# turbocharge.net
KiCad netlist of a schematic drawn in EAGLE
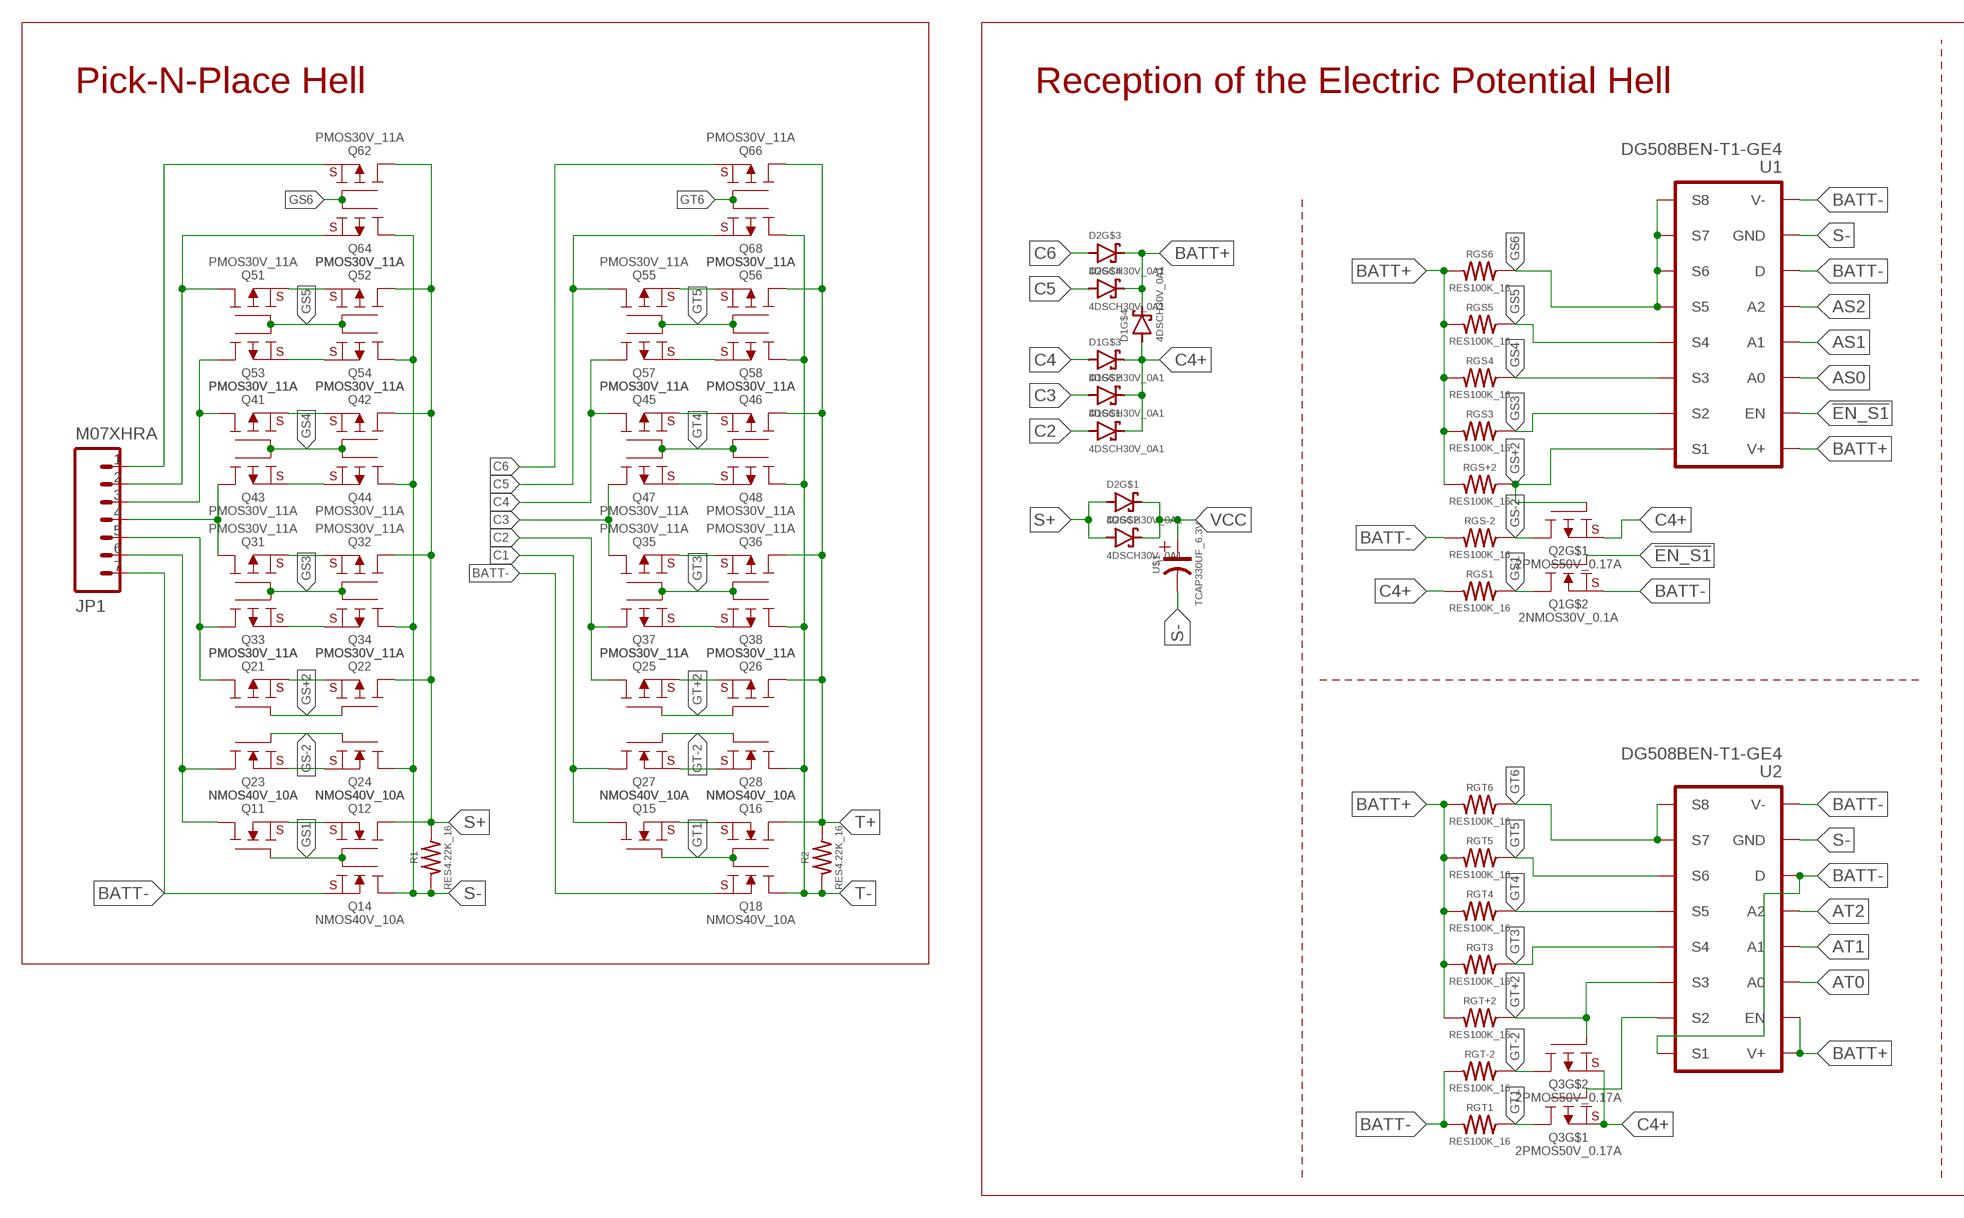
[diagram p0: schematic, sheet 1, part 1 of 2]
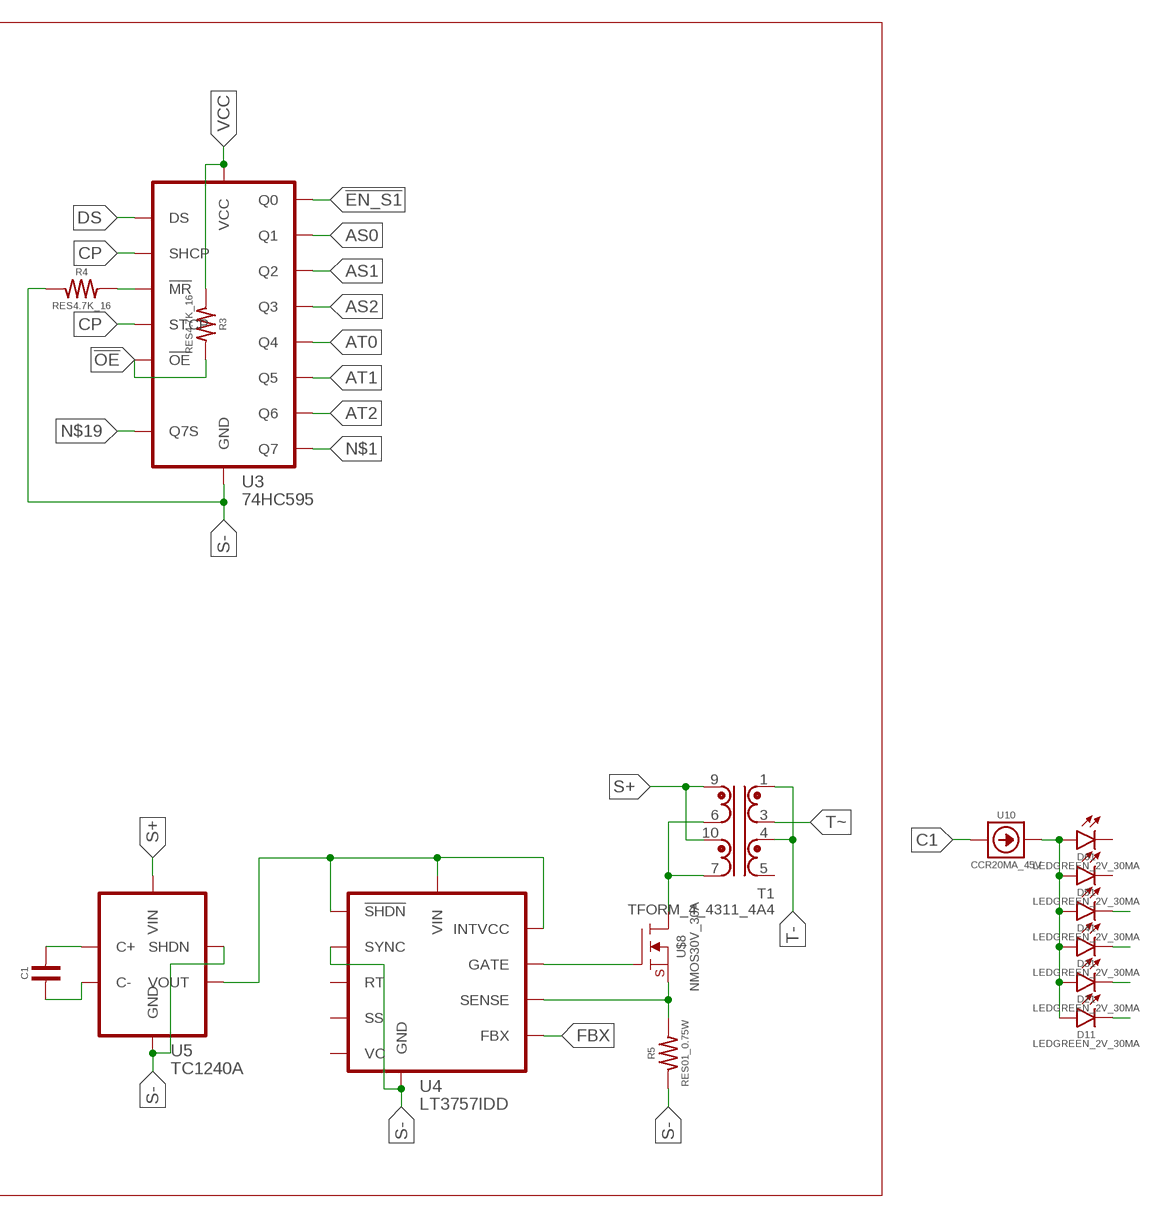
[diagram p1: schematic, sheet 1, part 2 of 2]

(export (version "E")
  (design (tool "Eeschema 10.0.6"))
  (components
    (comp (ref "C1")
      (value "CAP47UF_10V")
      (footprint "eagle-import:0805")
      (fields
        (field (name "DIGIKEY_PART_#") "445-8239-1-ND")
        (field (name "MANUFACTURER") "TDK Corporation")
        (field (name "MFG_PART_#") "C2012X5R1A476M125AC")
      )
      (libsource (lib "eagle-import") (part "CAP47UF_10V"))
    )
    (comp (ref "D1")
      (value "4DSCH30V_0A1")
      (footprint "eagle-import:8-HMD")
      (fields
        (field (name "DIGIKEY_PART_#") "RB521ZS8A30TE61CT-ND")
        (field (name "MANUFACTURER") "Rohm Semiconductor")
        (field (name "MFG_PART_#") "RB521ZS8A30TE61")
      )
      (libsource (lib "eagle-import") (part "4DSCH30V_0A1"))
    )
    (comp (ref "D2")
      (value "4DSCH30V_0A1")
      (footprint "eagle-import:8-HMD")
      (fields
        (field (name "DIGIKEY_PART_#") "RB521ZS8A30TE61CT-ND")
        (field (name "MANUFACTURER") "Rohm Semiconductor")
        (field (name "MFG_PART_#") "RB521ZS8A30TE61")
      )
      (libsource (lib "eagle-import") (part "4DSCH30V_0A1"))
    )
    (comp (ref "D11")
      (value "LEDGREEN_2V_30MA")
      (footprint "eagle-import:0603+")
      (fields
        (field (name "DIGIKEY_PART_#") "160-1435-1-ND")
        (field (name "MANUFACTURER") "Lite-On Inc.")
        (field (name "MFG_PART_#") "LTST-C190KGKT")
      )
      (libsource (lib "eagle-import") (part "LEDGREEN_2V_30MA"))
    )
    (comp (ref "D21")
      (value "LEDGREEN_2V_30MA")
      (footprint "eagle-import:0603+")
      (fields
        (field (name "DIGIKEY_PART_#") "160-1435-1-ND")
        (field (name "MANUFACTURER") "Lite-On Inc.")
        (field (name "MFG_PART_#") "LTST-C190KGKT")
      )
      (libsource (lib "eagle-import") (part "LEDGREEN_2V_30MA"))
    )
    (comp (ref "D31")
      (value "LEDGREEN_2V_30MA")
      (footprint "eagle-import:0603+")
      (fields
        (field (name "DIGIKEY_PART_#") "160-1435-1-ND")
        (field (name "MANUFACTURER") "Lite-On Inc.")
        (field (name "MFG_PART_#") "LTST-C190KGKT")
      )
      (libsource (lib "eagle-import") (part "LEDGREEN_2V_30MA"))
    )
    (comp (ref "D41")
      (value "LEDGREEN_2V_30MA")
      (footprint "eagle-import:0603+")
      (fields
        (field (name "DIGIKEY_PART_#") "160-1435-1-ND")
        (field (name "MANUFACTURER") "Lite-On Inc.")
        (field (name "MFG_PART_#") "LTST-C190KGKT")
      )
      (libsource (lib "eagle-import") (part "LEDGREEN_2V_30MA"))
    )
    (comp (ref "D51")
      (value "LEDGREEN_2V_30MA")
      (footprint "eagle-import:0603+")
      (fields
        (field (name "DIGIKEY_PART_#") "160-1435-1-ND")
        (field (name "MANUFACTURER") "Lite-On Inc.")
        (field (name "MFG_PART_#") "LTST-C190KGKT")
      )
      (libsource (lib "eagle-import") (part "LEDGREEN_2V_30MA"))
    )
    (comp (ref "D61")
      (value "LEDGREEN_2V_30MA")
      (footprint "eagle-import:0603+")
      (fields
        (field (name "DIGIKEY_PART_#") "160-1435-1-ND")
        (field (name "MANUFACTURER") "Lite-On Inc.")
        (field (name "MFG_PART_#") "LTST-C190KGKT")
      )
      (libsource (lib "eagle-import") (part "LEDGREEN_2V_30MA"))
    )
    (comp (ref "JP1")
      (value "M07XHRA")
      (footprint "eagle-import:XH07-RA")
      (fields
        (field (name "DIGIKEY_PART_#") "455-2240-ND")
        (field (name "MANUFACTURER") "JST Sales America Inc.")
        (field (name "MFG_PART_#") "S7B-XH-A(LF)(SN)")
      )
      (libsource (lib "eagle-import") (part "M07XHRA"))
    )
    (comp (ref "Q1")
      (value "2NMOS30V_0.1A")
      (footprint "eagle-import:SOT-666")
      (fields
        (field (name "DIGIKEY_PART_#") "FC6943010RCT-ND")
        (field (name "MANUFACTURER") "Panasonic Electronic Components")
        (field (name "MFG_PART_#") "FC6943010R")
      )
      (libsource (lib "eagle-import") (part "2NMOS30V_0.1A"))
    )
    (comp (ref "Q2")
      (value "2PMOS50V_0.17A")
      (footprint "eagle-import:SOT-666")
      (fields
        (field (name "DIGIKEY_PART_#") "568-10474-1-ND")
        (field (name "MANUFACTURER") "NXP Semiconductors")
        (field (name "MFG_PART_#") "BSS84AKV,115")
      )
      (libsource (lib "eagle-import") (part "2PMOS50V_0.17A"))
    )
    (comp (ref "Q3")
      (value "2PMOS50V_0.17A")
      (footprint "eagle-import:SOT-666")
      (fields
        (field (name "DIGIKEY_PART_#") "568-10474-1-ND")
        (field (name "MANUFACTURER") "NXP Semiconductors")
        (field (name "MFG_PART_#") "BSS84AKV,115")
      )
      (libsource (lib "eagle-import") (part "2PMOS50V_0.17A"))
    )
    (comp (ref "Q11")
      (value "NMOS40V_10A")
      (footprint "eagle-import:6-POWERWDFN")
      (fields
        (field (name "DIGIKEY_PART_#") "FDMA7670CT-ND")
        (field (name "MANUFACTURER") "Fairchild Semiconductor")
        (field (name "MFG_PART_#") "FDMA7670")
      )
      (libsource (lib "eagle-import") (part "NMOS40V_10A"))
    )
    (comp (ref "Q12")
      (value "NMOS40V_10A")
      (footprint "eagle-import:6-POWERWDFN")
      (fields
        (field (name "DIGIKEY_PART_#") "FDMA7670CT-ND")
        (field (name "MANUFACTURER") "Fairchild Semiconductor")
        (field (name "MFG_PART_#") "FDMA7670")
      )
      (libsource (lib "eagle-import") (part "NMOS40V_10A"))
    )
    (comp (ref "Q14")
      (value "NMOS40V_10A")
      (footprint "eagle-import:6-POWERWDFN")
      (fields
        (field (name "DIGIKEY_PART_#") "FDMA7670CT-ND")
        (field (name "MANUFACTURER") "Fairchild Semiconductor")
        (field (name "MFG_PART_#") "FDMA7670")
      )
      (libsource (lib "eagle-import") (part "NMOS40V_10A"))
    )
    (comp (ref "Q15")
      (value "NMOS40V_10A")
      (footprint "eagle-import:6-POWERWDFN")
      (fields
        (field (name "DIGIKEY_PART_#") "FDMA7670CT-ND")
        (field (name "MANUFACTURER") "Fairchild Semiconductor")
        (field (name "MFG_PART_#") "FDMA7670")
      )
      (libsource (lib "eagle-import") (part "NMOS40V_10A"))
    )
    (comp (ref "Q16")
      (value "NMOS40V_10A")
      (footprint "eagle-import:6-POWERWDFN")
      (fields
        (field (name "DIGIKEY_PART_#") "FDMA7670CT-ND")
        (field (name "MANUFACTURER") "Fairchild Semiconductor")
        (field (name "MFG_PART_#") "FDMA7670")
      )
      (libsource (lib "eagle-import") (part "NMOS40V_10A"))
    )
    (comp (ref "Q18")
      (value "NMOS40V_10A")
      (footprint "eagle-import:6-POWERWDFN")
      (fields
        (field (name "DIGIKEY_PART_#") "FDMA7670CT-ND")
        (field (name "MANUFACTURER") "Fairchild Semiconductor")
        (field (name "MFG_PART_#") "FDMA7670")
      )
      (libsource (lib "eagle-import") (part "NMOS40V_10A"))
    )
    (comp (ref "Q21")
      (value "PMOS30V_11A")
      (footprint "eagle-import:6-POWERWDFN")
      (fields
        (field (name "DIGIKEY_PART_#") "FDMA6676PZCT-ND")
        (field (name "MANUFACTURER") "Fairchild Semiconductor")
        (field (name "MFG_PART_#") "FDMA6676PZ")
      )
      (libsource (lib "eagle-import") (part "PMOS30V_11A"))
    )
    (comp (ref "Q22")
      (value "PMOS30V_11A")
      (footprint "eagle-import:6-POWERWDFN")
      (fields
        (field (name "DIGIKEY_PART_#") "FDMA6676PZCT-ND")
        (field (name "MANUFACTURER") "Fairchild Semiconductor")
        (field (name "MFG_PART_#") "FDMA6676PZ")
      )
      (libsource (lib "eagle-import") (part "PMOS30V_11A"))
    )
    (comp (ref "Q23")
      (value "NMOS40V_10A")
      (footprint "eagle-import:6-POWERWDFN")
      (fields
        (field (name "DIGIKEY_PART_#") "FDMA7670CT-ND")
        (field (name "MANUFACTURER") "Fairchild Semiconductor")
        (field (name "MFG_PART_#") "FDMA7670")
      )
      (libsource (lib "eagle-import") (part "NMOS40V_10A"))
    )
    (comp (ref "Q24")
      (value "NMOS40V_10A")
      (footprint "eagle-import:6-POWERWDFN")
      (fields
        (field (name "DIGIKEY_PART_#") "FDMA7670CT-ND")
        (field (name "MANUFACTURER") "Fairchild Semiconductor")
        (field (name "MFG_PART_#") "FDMA7670")
      )
      (libsource (lib "eagle-import") (part "NMOS40V_10A"))
    )
    (comp (ref "Q25")
      (value "PMOS30V_11A")
      (footprint "eagle-import:6-POWERWDFN")
      (fields
        (field (name "DIGIKEY_PART_#") "FDMA6676PZCT-ND")
        (field (name "MANUFACTURER") "Fairchild Semiconductor")
        (field (name "MFG_PART_#") "FDMA6676PZ")
      )
      (libsource (lib "eagle-import") (part "PMOS30V_11A"))
    )
    (comp (ref "Q26")
      (value "PMOS30V_11A")
      (footprint "eagle-import:6-POWERWDFN")
      (fields
        (field (name "DIGIKEY_PART_#") "FDMA6676PZCT-ND")
        (field (name "MANUFACTURER") "Fairchild Semiconductor")
        (field (name "MFG_PART_#") "FDMA6676PZ")
      )
      (libsource (lib "eagle-import") (part "PMOS30V_11A"))
    )
    (comp (ref "Q27")
      (value "NMOS40V_10A")
      (footprint "eagle-import:6-POWERWDFN")
      (fields
        (field (name "DIGIKEY_PART_#") "FDMA7670CT-ND")
        (field (name "MANUFACTURER") "Fairchild Semiconductor")
        (field (name "MFG_PART_#") "FDMA7670")
      )
      (libsource (lib "eagle-import") (part "NMOS40V_10A"))
    )
    (comp (ref "Q28")
      (value "NMOS40V_10A")
      (footprint "eagle-import:6-POWERWDFN")
      (fields
        (field (name "DIGIKEY_PART_#") "FDMA7670CT-ND")
        (field (name "MANUFACTURER") "Fairchild Semiconductor")
        (field (name "MFG_PART_#") "FDMA7670")
      )
      (libsource (lib "eagle-import") (part "NMOS40V_10A"))
    )
    (comp (ref "Q31")
      (value "PMOS30V_11A")
      (footprint "eagle-import:6-POWERWDFN")
      (fields
        (field (name "DIGIKEY_PART_#") "FDMA6676PZCT-ND")
        (field (name "MANUFACTURER") "Fairchild Semiconductor")
        (field (name "MFG_PART_#") "FDMA6676PZ")
      )
      (libsource (lib "eagle-import") (part "PMOS30V_11A"))
    )
    (comp (ref "Q32")
      (value "PMOS30V_11A")
      (footprint "eagle-import:6-POWERWDFN")
      (fields
        (field (name "DIGIKEY_PART_#") "FDMA6676PZCT-ND")
        (field (name "MANUFACTURER") "Fairchild Semiconductor")
        (field (name "MFG_PART_#") "FDMA6676PZ")
      )
      (libsource (lib "eagle-import") (part "PMOS30V_11A"))
    )
    (comp (ref "Q33")
      (value "PMOS30V_11A")
      (footprint "eagle-import:6-POWERWDFN")
      (fields
        (field (name "DIGIKEY_PART_#") "FDMA6676PZCT-ND")
        (field (name "MANUFACTURER") "Fairchild Semiconductor")
        (field (name "MFG_PART_#") "FDMA6676PZ")
      )
      (libsource (lib "eagle-import") (part "PMOS30V_11A"))
    )
    (comp (ref "Q34")
      (value "PMOS30V_11A")
      (footprint "eagle-import:6-POWERWDFN")
      (fields
        (field (name "DIGIKEY_PART_#") "FDMA6676PZCT-ND")
        (field (name "MANUFACTURER") "Fairchild Semiconductor")
        (field (name "MFG_PART_#") "FDMA6676PZ")
      )
      (libsource (lib "eagle-import") (part "PMOS30V_11A"))
    )
    (comp (ref "Q35")
      (value "PMOS30V_11A")
      (footprint "eagle-import:6-POWERWDFN")
      (fields
        (field (name "DIGIKEY_PART_#") "FDMA6676PZCT-ND")
        (field (name "MANUFACTURER") "Fairchild Semiconductor")
        (field (name "MFG_PART_#") "FDMA6676PZ")
      )
      (libsource (lib "eagle-import") (part "PMOS30V_11A"))
    )
    (comp (ref "Q36")
      (value "PMOS30V_11A")
      (footprint "eagle-import:6-POWERWDFN")
      (fields
        (field (name "DIGIKEY_PART_#") "FDMA6676PZCT-ND")
        (field (name "MANUFACTURER") "Fairchild Semiconductor")
        (field (name "MFG_PART_#") "FDMA6676PZ")
      )
      (libsource (lib "eagle-import") (part "PMOS30V_11A"))
    )
    (comp (ref "Q37")
      (value "PMOS30V_11A")
      (footprint "eagle-import:6-POWERWDFN")
      (fields
        (field (name "DIGIKEY_PART_#") "FDMA6676PZCT-ND")
        (field (name "MANUFACTURER") "Fairchild Semiconductor")
        (field (name "MFG_PART_#") "FDMA6676PZ")
      )
      (libsource (lib "eagle-import") (part "PMOS30V_11A"))
    )
    (comp (ref "Q38")
      (value "PMOS30V_11A")
      (footprint "eagle-import:6-POWERWDFN")
      (fields
        (field (name "DIGIKEY_PART_#") "FDMA6676PZCT-ND")
        (field (name "MANUFACTURER") "Fairchild Semiconductor")
        (field (name "MFG_PART_#") "FDMA6676PZ")
      )
      (libsource (lib "eagle-import") (part "PMOS30V_11A"))
    )
    (comp (ref "Q41")
      (value "PMOS30V_11A")
      (footprint "eagle-import:6-POWERWDFN")
      (fields
        (field (name "DIGIKEY_PART_#") "FDMA6676PZCT-ND")
        (field (name "MANUFACTURER") "Fairchild Semiconductor")
        (field (name "MFG_PART_#") "FDMA6676PZ")
      )
      (libsource (lib "eagle-import") (part "PMOS30V_11A"))
    )
    (comp (ref "Q42")
      (value "PMOS30V_11A")
      (footprint "eagle-import:6-POWERWDFN")
      (fields
        (field (name "DIGIKEY_PART_#") "FDMA6676PZCT-ND")
        (field (name "MANUFACTURER") "Fairchild Semiconductor")
        (field (name "MFG_PART_#") "FDMA6676PZ")
      )
      (libsource (lib "eagle-import") (part "PMOS30V_11A"))
    )
    (comp (ref "Q43")
      (value "PMOS30V_11A")
      (footprint "eagle-import:6-POWERWDFN")
      (fields
        (field (name "DIGIKEY_PART_#") "FDMA6676PZCT-ND")
        (field (name "MANUFACTURER") "Fairchild Semiconductor")
        (field (name "MFG_PART_#") "FDMA6676PZ")
      )
      (libsource (lib "eagle-import") (part "PMOS30V_11A"))
    )
    (comp (ref "Q44")
      (value "PMOS30V_11A")
      (footprint "eagle-import:6-POWERWDFN")
      (fields
        (field (name "DIGIKEY_PART_#") "FDMA6676PZCT-ND")
        (field (name "MANUFACTURER") "Fairchild Semiconductor")
        (field (name "MFG_PART_#") "FDMA6676PZ")
      )
      (libsource (lib "eagle-import") (part "PMOS30V_11A"))
    )
    (comp (ref "Q45")
      (value "PMOS30V_11A")
      (footprint "eagle-import:6-POWERWDFN")
      (fields
        (field (name "DIGIKEY_PART_#") "FDMA6676PZCT-ND")
        (field (name "MANUFACTURER") "Fairchild Semiconductor")
        (field (name "MFG_PART_#") "FDMA6676PZ")
      )
      (libsource (lib "eagle-import") (part "PMOS30V_11A"))
    )
    (comp (ref "Q46")
      (value "PMOS30V_11A")
      (footprint "eagle-import:6-POWERWDFN")
      (fields
        (field (name "DIGIKEY_PART_#") "FDMA6676PZCT-ND")
        (field (name "MANUFACTURER") "Fairchild Semiconductor")
        (field (name "MFG_PART_#") "FDMA6676PZ")
      )
      (libsource (lib "eagle-import") (part "PMOS30V_11A"))
    )
    (comp (ref "Q47")
      (value "PMOS30V_11A")
      (footprint "eagle-import:6-POWERWDFN")
      (fields
        (field (name "DIGIKEY_PART_#") "FDMA6676PZCT-ND")
        (field (name "MANUFACTURER") "Fairchild Semiconductor")
        (field (name "MFG_PART_#") "FDMA6676PZ")
      )
      (libsource (lib "eagle-import") (part "PMOS30V_11A"))
    )
    (comp (ref "Q48")
      (value "PMOS30V_11A")
      (footprint "eagle-import:6-POWERWDFN")
      (fields
        (field (name "DIGIKEY_PART_#") "FDMA6676PZCT-ND")
        (field (name "MANUFACTURER") "Fairchild Semiconductor")
        (field (name "MFG_PART_#") "FDMA6676PZ")
      )
      (libsource (lib "eagle-import") (part "PMOS30V_11A"))
    )
    (comp (ref "Q51")
      (value "PMOS30V_11A")
      (footprint "eagle-import:6-POWERWDFN")
      (fields
        (field (name "DIGIKEY_PART_#") "FDMA6676PZCT-ND")
        (field (name "MANUFACTURER") "Fairchild Semiconductor")
        (field (name "MFG_PART_#") "FDMA6676PZ")
      )
      (libsource (lib "eagle-import") (part "PMOS30V_11A"))
    )
    (comp (ref "Q52")
      (value "PMOS30V_11A")
      (footprint "eagle-import:6-POWERWDFN")
      (fields
        (field (name "DIGIKEY_PART_#") "FDMA6676PZCT-ND")
        (field (name "MANUFACTURER") "Fairchild Semiconductor")
        (field (name "MFG_PART_#") "FDMA6676PZ")
      )
      (libsource (lib "eagle-import") (part "PMOS30V_11A"))
    )
    (comp (ref "Q53")
      (value "PMOS30V_11A")
      (footprint "eagle-import:6-POWERWDFN")
      (fields
        (field (name "DIGIKEY_PART_#") "FDMA6676PZCT-ND")
        (field (name "MANUFACTURER") "Fairchild Semiconductor")
        (field (name "MFG_PART_#") "FDMA6676PZ")
      )
      (libsource (lib "eagle-import") (part "PMOS30V_11A"))
    )
    (comp (ref "Q54")
      (value "PMOS30V_11A")
      (footprint "eagle-import:6-POWERWDFN")
      (fields
        (field (name "DIGIKEY_PART_#") "FDMA6676PZCT-ND")
        (field (name "MANUFACTURER") "Fairchild Semiconductor")
        (field (name "MFG_PART_#") "FDMA6676PZ")
      )
      (libsource (lib "eagle-import") (part "PMOS30V_11A"))
    )
    (comp (ref "Q55")
      (value "PMOS30V_11A")
      (footprint "eagle-import:6-POWERWDFN")
      (fields
        (field (name "DIGIKEY_PART_#") "FDMA6676PZCT-ND")
        (field (name "MANUFACTURER") "Fairchild Semiconductor")
        (field (name "MFG_PART_#") "FDMA6676PZ")
      )
      (libsource (lib "eagle-import") (part "PMOS30V_11A"))
    )
    (comp (ref "Q56")
      (value "PMOS30V_11A")
      (footprint "eagle-import:6-POWERWDFN")
      (fields
        (field (name "DIGIKEY_PART_#") "FDMA6676PZCT-ND")
        (field (name "MANUFACTURER") "Fairchild Semiconductor")
        (field (name "MFG_PART_#") "FDMA6676PZ")
      )
      (libsource (lib "eagle-import") (part "PMOS30V_11A"))
    )
    (comp (ref "Q57")
      (value "PMOS30V_11A")
      (footprint "eagle-import:6-POWERWDFN")
      (fields
        (field (name "DIGIKEY_PART_#") "FDMA6676PZCT-ND")
        (field (name "MANUFACTURER") "Fairchild Semiconductor")
        (field (name "MFG_PART_#") "FDMA6676PZ")
      )
      (libsource (lib "eagle-import") (part "PMOS30V_11A"))
    )
    (comp (ref "Q58")
      (value "PMOS30V_11A")
      (footprint "eagle-import:6-POWERWDFN")
      (fields
        (field (name "DIGIKEY_PART_#") "FDMA6676PZCT-ND")
        (field (name "MANUFACTURER") "Fairchild Semiconductor")
        (field (name "MFG_PART_#") "FDMA6676PZ")
      )
      (libsource (lib "eagle-import") (part "PMOS30V_11A"))
    )
    (comp (ref "Q62")
      (value "PMOS30V_11A")
      (footprint "eagle-import:6-POWERWDFN")
      (fields
        (field (name "DIGIKEY_PART_#") "FDMA6676PZCT-ND")
        (field (name "MANUFACTURER") "Fairchild Semiconductor")
        (field (name "MFG_PART_#") "FDMA6676PZ")
      )
      (libsource (lib "eagle-import") (part "PMOS30V_11A"))
    )
    (comp (ref "Q64")
      (value "PMOS30V_11A")
      (footprint "eagle-import:6-POWERWDFN")
      (fields
        (field (name "DIGIKEY_PART_#") "FDMA6676PZCT-ND")
        (field (name "MANUFACTURER") "Fairchild Semiconductor")
        (field (name "MFG_PART_#") "FDMA6676PZ")
      )
      (libsource (lib "eagle-import") (part "PMOS30V_11A"))
    )
    (comp (ref "Q66")
      (value "PMOS30V_11A")
      (footprint "eagle-import:6-POWERWDFN")
      (fields
        (field (name "DIGIKEY_PART_#") "FDMA6676PZCT-ND")
        (field (name "MANUFACTURER") "Fairchild Semiconductor")
        (field (name "MFG_PART_#") "FDMA6676PZ")
      )
      (libsource (lib "eagle-import") (part "PMOS30V_11A"))
    )
    (comp (ref "Q68")
      (value "PMOS30V_11A")
      (footprint "eagle-import:6-POWERWDFN")
      (fields
        (field (name "DIGIKEY_PART_#") "FDMA6676PZCT-ND")
        (field (name "MANUFACTURER") "Fairchild Semiconductor")
        (field (name "MFG_PART_#") "FDMA6676PZ")
      )
      (libsource (lib "eagle-import") (part "PMOS30V_11A"))
    )
    (comp (ref "R1")
      (value "RES4.22K_16")
      (footprint "eagle-import:0402")
      (fields
        (field (name "DIGIKEY_PART_#") "541-4.22KLCT-ND")
        (field (name "MANUFACTURER") "Vishay Dale")
        (field (name "MFG_PART_#") "CRCW04024K22FKED")
      )
      (libsource (lib "eagle-import") (part "RES4.22K_16"))
    )
    (comp (ref "R2")
      (value "RES4.22K_16")
      (footprint "eagle-import:0402")
      (fields
        (field (name "DIGIKEY_PART_#") "541-4.22KLCT-ND")
        (field (name "MANUFACTURER") "Vishay Dale")
        (field (name "MFG_PART_#") "CRCW04024K22FKED")
      )
      (libsource (lib "eagle-import") (part "RES4.22K_16"))
    )
    (comp (ref "R3")
      (value "RES4.7K_16")
      (footprint "eagle-import:0402")
      (fields
        (field (name "DIGIKEY_PART_#") "541-4.70KLCT-ND")
        (field (name "MANUFACTURER") "Vishay Dale")
        (field (name "MFG_PART_#") "CRCW04024K70FKED")
      )
      (libsource (lib "eagle-import") (part "RES4.7K_16"))
    )
    (comp (ref "R4")
      (value "RES4.7K_16")
      (footprint "eagle-import:0402")
      (fields
        (field (name "DIGIKEY_PART_#") "541-4.70KLCT-ND")
        (field (name "MANUFACTURER") "Vishay Dale")
        (field (name "MFG_PART_#") "CRCW04024K70FKED")
      )
      (libsource (lib "eagle-import") (part "RES4.7K_16"))
    )
    (comp (ref "R5")
      (value "RES01_0.75W")
      (footprint "eagle-import:1206")
      (fields
        (field (name "DIGIKEY_PART_#") "408-1570-1-ND")
        (field (name "MANUFACTURER") "Susumu")
        (field (name "MFG_PART_#") "KRL1632E-M-R010-F-T5")
      )
      (libsource (lib "eagle-import") (part "RES01_0.75W"))
    )
    (comp (ref "RGS+2")
      (value "RES100K_16")
      (footprint "eagle-import:0402")
      (fields
        (field (name "DIGIKEY_PART_#") "541-100KLCT-ND")
        (field (name "MANUFACTURER") "Vishay Dale")
        (field (name "MFG_PART_#") "CRCW0402100KFKED")
      )
      (libsource (lib "eagle-import") (part "RES100K_16"))
    )
    (comp (ref "RGS-2")
      (value "RES100K_16")
      (footprint "eagle-import:0402")
      (fields
        (field (name "DIGIKEY_PART_#") "541-100KLCT-ND")
        (field (name "MANUFACTURER") "Vishay Dale")
        (field (name "MFG_PART_#") "CRCW0402100KFKED")
      )
      (libsource (lib "eagle-import") (part "RES100K_16"))
    )
    (comp (ref "RGS1")
      (value "RES100K_16")
      (footprint "eagle-import:0402")
      (fields
        (field (name "DIGIKEY_PART_#") "541-100KLCT-ND")
        (field (name "MANUFACTURER") "Vishay Dale")
        (field (name "MFG_PART_#") "CRCW0402100KFKED")
      )
      (libsource (lib "eagle-import") (part "RES100K_16"))
    )
    (comp (ref "RGS3")
      (value "RES100K_16")
      (footprint "eagle-import:0402")
      (fields
        (field (name "DIGIKEY_PART_#") "541-100KLCT-ND")
        (field (name "MANUFACTURER") "Vishay Dale")
        (field (name "MFG_PART_#") "CRCW0402100KFKED")
      )
      (libsource (lib "eagle-import") (part "RES100K_16"))
    )
    (comp (ref "RGS4")
      (value "RES100K_16")
      (footprint "eagle-import:0402")
      (fields
        (field (name "DIGIKEY_PART_#") "541-100KLCT-ND")
        (field (name "MANUFACTURER") "Vishay Dale")
        (field (name "MFG_PART_#") "CRCW0402100KFKED")
      )
      (libsource (lib "eagle-import") (part "RES100K_16"))
    )
    (comp (ref "RGS5")
      (value "RES100K_16")
      (footprint "eagle-import:0402")
      (fields
        (field (name "DIGIKEY_PART_#") "541-100KLCT-ND")
        (field (name "MANUFACTURER") "Vishay Dale")
        (field (name "MFG_PART_#") "CRCW0402100KFKED")
      )
      (libsource (lib "eagle-import") (part "RES100K_16"))
    )
    (comp (ref "RGS6")
      (value "RES100K_16")
      (footprint "eagle-import:0402")
      (fields
        (field (name "DIGIKEY_PART_#") "541-100KLCT-ND")
        (field (name "MANUFACTURER") "Vishay Dale")
        (field (name "MFG_PART_#") "CRCW0402100KFKED")
      )
      (libsource (lib "eagle-import") (part "RES100K_16"))
    )
    (comp (ref "RGT+2")
      (value "RES100K_16")
      (footprint "eagle-import:0402")
      (fields
        (field (name "DIGIKEY_PART_#") "541-100KLCT-ND")
        (field (name "MANUFACTURER") "Vishay Dale")
        (field (name "MFG_PART_#") "CRCW0402100KFKED")
      )
      (libsource (lib "eagle-import") (part "RES100K_16"))
    )
    (comp (ref "RGT-2")
      (value "RES100K_16")
      (footprint "eagle-import:0402")
      (fields
        (field (name "DIGIKEY_PART_#") "541-100KLCT-ND")
        (field (name "MANUFACTURER") "Vishay Dale")
        (field (name "MFG_PART_#") "CRCW0402100KFKED")
      )
      (libsource (lib "eagle-import") (part "RES100K_16"))
    )
    (comp (ref "RGT1")
      (value "RES100K_16")
      (footprint "eagle-import:0402")
      (fields
        (field (name "DIGIKEY_PART_#") "541-100KLCT-ND")
        (field (name "MANUFACTURER") "Vishay Dale")
        (field (name "MFG_PART_#") "CRCW0402100KFKED")
      )
      (libsource (lib "eagle-import") (part "RES100K_16"))
    )
    (comp (ref "RGT3")
      (value "RES100K_16")
      (footprint "eagle-import:0402")
      (fields
        (field (name "DIGIKEY_PART_#") "541-100KLCT-ND")
        (field (name "MANUFACTURER") "Vishay Dale")
        (field (name "MFG_PART_#") "CRCW0402100KFKED")
      )
      (libsource (lib "eagle-import") (part "RES100K_16"))
    )
    (comp (ref "RGT4")
      (value "RES100K_16")
      (footprint "eagle-import:0402")
      (fields
        (field (name "DIGIKEY_PART_#") "541-100KLCT-ND")
        (field (name "MANUFACTURER") "Vishay Dale")
        (field (name "MFG_PART_#") "CRCW0402100KFKED")
      )
      (libsource (lib "eagle-import") (part "RES100K_16"))
    )
    (comp (ref "RGT5")
      (value "RES100K_16")
      (footprint "eagle-import:0402")
      (fields
        (field (name "DIGIKEY_PART_#") "541-100KLCT-ND")
        (field (name "MANUFACTURER") "Vishay Dale")
        (field (name "MFG_PART_#") "CRCW0402100KFKED")
      )
      (libsource (lib "eagle-import") (part "RES100K_16"))
    )
    (comp (ref "RGT6")
      (value "RES100K_16")
      (footprint "eagle-import:0402")
      (fields
        (field (name "DIGIKEY_PART_#") "541-100KLCT-ND")
        (field (name "MANUFACTURER") "Vishay Dale")
        (field (name "MFG_PART_#") "CRCW0402100KFKED")
      )
      (libsource (lib "eagle-import") (part "RES100K_16"))
    )
    (comp (ref "T1")
      (value "TFORM_4_4311_4A4")
      (footprint "eagle-import:EPQ13")
      (fields
        (field (name "DIGIKEY_PART_#") "732-6198-1-ND")
        (field (name "MANUFACTURER") "Wurth Electronics Inc")
        (field (name "MFG_PART_#") "7491195501")
      )
      (libsource (lib "eagle-import") (part "TFORM_4_4311_4A4"))
    )
    (comp (ref "U$1")
      (value "TCAP330UF_6.3V")
      (footprint "eagle-import:1210+")
      (fields
        (field (name "DIGIKEY_PART_#") "478-8407-1-ND")
        (field (name "MANUFACTURER") "AVX Corporation")
        (field (name "MFG_PART_#") "F950J337KBAAQ2")
      )
      (libsource (lib "eagle-import") (part "TCAP330UF_6.3V"))
    )
    (comp (ref "U$8")
      (value "NMOS30V_30A")
      (footprint "eagle-import:8-POWERWDFN")
      (fields
        (field (name "DIGIKEY_PART_#") "FDMC8010ET30CT-ND")
        (field (name "MANUFACTURER") "Fairchild Semiconductor")
        (field (name "MFG_PART_#") "FDMC8010ET30")
      )
      (libsource (lib "eagle-import") (part "NMOS30V_30A"))
    )
    (comp (ref "U1")
      (value "DG508BEN-T1-GE4")
      (footprint "eagle-import:MINIQFN-16L")
      (fields
        (field (name "MANUFACTURER") "Vishay Siliconix")
        (field (name "MOUSER_PART_#") "78-DG508BEN-T1-GE4")
      )
      (libsource (lib "eagle-import") (part "DG508BEN-T1-GE4"))
    )
    (comp (ref "U2")
      (value "DG508BEN-T1-GE4")
      (footprint "eagle-import:MINIQFN-16L")
      (fields
        (field (name "MANUFACTURER") "Vishay Siliconix")
        (field (name "MOUSER_PART_#") "78-DG508BEN-T1-GE4")
      )
      (libsource (lib "eagle-import") (part "DG508BEN-T1-GE4"))
    )
    (comp (ref "U3")
      (value "74HC595")
      (footprint "eagle-import:16-VFQFN")
      (fields
        (field (name "DIGIKEY_PART_#") "568-2719-1-ND")
        (field (name "MANUFACTURER") "NXP Semiconductors")
        (field (name "MFG_PART_#") "74HC595BQ,115")
      )
      (libsource (lib "eagle-import") (part "74HC595"))
    )
    (comp (ref "U4")
      (value "LT3757IDD")
      (footprint "eagle-import:10-WFDFN")
      (fields
        (field (name "DIGIKEY_PART_#") "LT3757IDD#PBF-ND")
        (field (name "MANUFACTURER") "Linear Technology")
        (field (name "MFG_PART_#") "LT3757IDD#PBF")
      )
      (libsource (lib "eagle-import") (part "LT3757IDD"))
    )
    (comp (ref "U5")
      (value "TC1240A")
      (footprint "eagle-import:SOT-23-6")
      (fields
        (field (name "DIGIKEY_PART_#") "TC1240AECHCT-ND")
        (field (name "MANUFACTURER") "Microchip Technology")
        (field (name "MFG_PART_#") "TC1240AECHTR")
      )
      (libsource (lib "eagle-import") (part "TC1240A"))
    )
    (comp (ref "U10")
      (value "CCR20MA_45V")
      (footprint "eagle-import:SOD-123")
      (fields
        (field (name "DIGIKEY_PART_#") "NSI45020T1GOSCT-ND")
        (field (name "MANUFACTURER") "ON Semiconductor")
        (field (name "MFG_PART_#") "NSI45020T1G")
      )
      (libsource (lib "eagle-import") (part "CCR20MA_45V"))
    )
  )
  (nets
    (net (code "1") (name "/T~{}") (class "Default")
      (node (ref "T1") (pin "3") (pinfunction "2_3") (pintype "passive"))
    )
    (net (code "2") (name "/~{EN_S1}") (class "Default")
      (node (ref "Q1") (pin "5") (pinfunction "G_5") (pintype "passive"))
      (node (ref "U1") (pin "16") (pinfunction "EN_16") (pintype "passive"))
      (node (ref "U3") (pin "15") (pinfunction "Q0_15") (pintype "passive"))
    )
    (net (code "3") (name "/~{OE}") (class "Default")
      (node (ref "R3") (pin "2") (pinfunction "2_2") (pintype "passive"))
      (node (ref "U3") (pin "13") (pinfunction "~{OE}_13") (pintype "passive"))
    )
    (net (code "4") (name "AS0") (class "Default")
      (node (ref "U1") (pin "15") (pinfunction "A0_15") (pintype "passive"))
      (node (ref "U3") (pin "1") (pinfunction "Q1_1") (pintype "passive"))
    )
    (net (code "5") (name "AS1") (class "Default")
      (node (ref "U1") (pin "14") (pinfunction "A1_14") (pintype "passive"))
      (node (ref "U3") (pin "2") (pinfunction "Q2_2") (pintype "passive"))
    )
    (net (code "6") (name "AS2") (class "Default")
      (node (ref "U1") (pin "13") (pinfunction "A2_13") (pintype "passive"))
      (node (ref "U3") (pin "3") (pinfunction "Q3_3") (pintype "passive"))
    )
    (net (code "7") (name "AT0") (class "Default")
      (node (ref "U2") (pin "15") (pinfunction "A0_15") (pintype "passive"))
      (node (ref "U3") (pin "4") (pinfunction "Q4_4") (pintype "passive"))
    )
    (net (code "8") (name "AT1") (class "Default")
      (node (ref "U2") (pin "14") (pinfunction "A1_14") (pintype "passive"))
      (node (ref "U3") (pin "5") (pinfunction "Q5_5") (pintype "passive"))
    )
    (net (code "9") (name "AT2") (class "Default")
      (node (ref "U2") (pin "13") (pinfunction "A2_13") (pintype "passive"))
      (node (ref "U3") (pin "6") (pinfunction "Q6_6") (pintype "passive"))
    )
    (net (code "10") (name "BATT+") (class "Default")
      (node (ref "D1") (pin "5") (pinfunction "C_5") (pintype "passive"))
      (node (ref "D2") (pin "5") (pinfunction "C_5") (pintype "passive"))
      (node (ref "D2") (pin "6") (pinfunction "C_6") (pintype "passive"))
      (node (ref "RGS+2") (pin "1") (pinfunction "1_1") (pintype "passive"))
      (node (ref "RGS3") (pin "1") (pinfunction "1_1") (pintype "passive"))
      (node (ref "RGS4") (pin "1") (pinfunction "1_1") (pintype "passive"))
      (node (ref "RGS5") (pin "1") (pinfunction "1_1") (pintype "passive"))
      (node (ref "RGS6") (pin "1") (pinfunction "1_1") (pintype "passive"))
      (node (ref "RGT+2") (pin "1") (pinfunction "1_1") (pintype "passive"))
      (node (ref "RGT3") (pin "1") (pinfunction "1_1") (pintype "passive"))
      (node (ref "RGT4") (pin "1") (pinfunction "1_1") (pintype "passive"))
      (node (ref "RGT5") (pin "1") (pinfunction "1_1") (pintype "passive"))
      (node (ref "RGT6") (pin "1") (pinfunction "1_1") (pintype "passive"))
      (node (ref "U1") (pin "11") (pinfunction "V+_11") (pintype "passive"))
      (node (ref "U2") (pin "11") (pinfunction "V+_11") (pintype "passive"))
      (node (ref "U2") (pin "16") (pinfunction "EN_16") (pintype "passive"))
    )
    (net (code "11") (name "BATT-") (class "Default")
      (node (ref "JP1") (pin "7") (pinfunction "7_7") (pintype "passive"))
      (node (ref "Q1") (pin "4") (pinfunction "S_4") (pintype "passive"))
      (node (ref "Q14") (pin "S") (pinfunction "S_S") (pintype "passive"))
      (node (ref "Q18") (pin "S") (pinfunction "S_S") (pintype "passive"))
      (node (ref "RGS-2") (pin "1") (pinfunction "1_1") (pintype "passive"))
      (node (ref "RGT-2") (pin "1") (pinfunction "1_1") (pintype "passive"))
      (node (ref "RGT1") (pin "1") (pinfunction "1_1") (pintype "passive"))
      (node (ref "U1") (pin "1") (pinfunction "V-_1") (pintype "passive"))
      (node (ref "U1") (pin "6") (pinfunction "D_6") (pintype "passive"))
      (node (ref "U2") (pin "1") (pinfunction "V-_1") (pintype "passive"))
      (node (ref "U2") (pin "2") (pinfunction "S1_2") (pintype "passive"))
      (node (ref "U2") (pin "6") (pinfunction "D_6") (pintype "passive"))
    )
    (net (code "12") (name "C1") (class "Default")
      (node (ref "JP1") (pin "6") (pinfunction "6_6") (pintype "passive"))
      (node (ref "Q11") (pin "D") (pinfunction "D_D") (pintype "passive"))
      (node (ref "Q15") (pin "D") (pinfunction "D_D") (pintype "passive"))
      (node (ref "Q23") (pin "D") (pinfunction "D_D") (pintype "passive"))
      (node (ref "Q27") (pin "D") (pinfunction "D_D") (pintype "passive"))
      (node (ref "U10") (pin "A") (pinfunction "A_A") (pintype "passive"))
    )
    (net (code "13") (name "C2") (class "Default")
      (node (ref "D1") (pin "1") (pinfunction "A_1") (pintype "passive"))
      (node (ref "JP1") (pin "5") (pinfunction "5_5") (pintype "passive"))
      (node (ref "Q21") (pin "D") (pinfunction "D_D") (pintype "passive"))
      (node (ref "Q25") (pin "D") (pinfunction "D_D") (pintype "passive"))
      (node (ref "Q33") (pin "D") (pinfunction "D_D") (pintype "passive"))
      (node (ref "Q37") (pin "D") (pinfunction "D_D") (pintype "passive"))
    )
    (net (code "14") (name "C3") (class "Default")
      (node (ref "D1") (pin "2") (pinfunction "A_2") (pintype "passive"))
      (node (ref "JP1") (pin "4") (pinfunction "4_4") (pintype "passive"))
      (node (ref "Q31") (pin "D") (pinfunction "D_D") (pintype "passive"))
      (node (ref "Q35") (pin "D") (pinfunction "D_D") (pintype "passive"))
      (node (ref "Q43") (pin "D") (pinfunction "D_D") (pintype "passive"))
      (node (ref "Q47") (pin "D") (pinfunction "D_D") (pintype "passive"))
    )
    (net (code "15") (name "C4") (class "Default")
      (node (ref "D1") (pin "3") (pinfunction "A_3") (pintype "passive"))
      (node (ref "JP1") (pin "3") (pinfunction "3_3") (pintype "passive"))
      (node (ref "Q41") (pin "D") (pinfunction "D_D") (pintype "passive"))
      (node (ref "Q45") (pin "D") (pinfunction "D_D") (pintype "passive"))
      (node (ref "Q53") (pin "D") (pinfunction "D_D") (pintype "passive"))
      (node (ref "Q57") (pin "D") (pinfunction "D_D") (pintype "passive"))
    )
    (net (code "16") (name "C4+") (class "Default")
      (node (ref "D1") (pin "4") (pinfunction "A_4") (pintype "passive"))
      (node (ref "D1") (pin "6") (pinfunction "C_6") (pintype "passive"))
      (node (ref "D1") (pin "7") (pinfunction "C_7") (pintype "passive"))
      (node (ref "D1") (pin "8") (pinfunction "C_8") (pintype "passive"))
      (node (ref "Q2") (pin "1") (pinfunction "S_1") (pintype "passive"))
      (node (ref "Q3") (pin "1") (pinfunction "S_1") (pintype "passive"))
      (node (ref "Q3") (pin "4") (pinfunction "S_4") (pintype "passive"))
      (node (ref "RGS1") (pin "1") (pinfunction "1_1") (pintype "passive"))
    )
    (net (code "17") (name "C5") (class "Default")
      (node (ref "D2") (pin "4") (pinfunction "A_4") (pintype "passive"))
      (node (ref "JP1") (pin "2") (pinfunction "2_2") (pintype "passive"))
      (node (ref "Q51") (pin "D") (pinfunction "D_D") (pintype "passive"))
      (node (ref "Q55") (pin "D") (pinfunction "D_D") (pintype "passive"))
      (node (ref "Q64") (pin "S") (pinfunction "S_S") (pintype "passive"))
      (node (ref "Q68") (pin "S") (pinfunction "S_S") (pintype "passive"))
    )
    (net (code "18") (name "C6") (class "Default")
      (node (ref "D2") (pin "3") (pinfunction "A_3") (pintype "passive"))
      (node (ref "JP1") (pin "1") (pinfunction "1_1") (pintype "passive"))
      (node (ref "Q62") (pin "S") (pinfunction "S_S") (pintype "passive"))
      (node (ref "Q66") (pin "S") (pinfunction "S_S") (pintype "passive"))
    )
    (net (code "19") (name "CP") (class "Default")
      (node (ref "U3") (pin "11") (pinfunction "SHCP_11") (pintype "passive"))
      (node (ref "U3") (pin "12") (pinfunction "STCP_12") (pintype "passive"))
    )
    (net (code "20") (name "DS") (class "Default")
      (node (ref "U3") (pin "14") (pinfunction "DS_14") (pintype "passive"))
    )
    (net (code "21") (name "FBX") (class "Default")
      (node (ref "U4") (pin "2") (pinfunction "FBX_2") (pintype "passive"))
    )
    (net (code "22") (name "GS+2") (class "Default")
      (node (ref "Q2") (pin "2") (pinfunction "G_2") (pintype "passive"))
      (node (ref "Q21") (pin "G") (pinfunction "G_G") (pintype "passive"))
      (node (ref "Q22") (pin "G") (pinfunction "G_G") (pintype "passive"))
      (node (ref "RGS+2") (pin "2") (pinfunction "2_2") (pintype "passive"))
      (node (ref "U1") (pin "2") (pinfunction "S1_2") (pintype "passive"))
    )
    (net (code "23") (name "GS-2") (class "Default")
      (node (ref "Q2") (pin "6") (pinfunction "D_6") (pintype "passive"))
      (node (ref "Q23") (pin "G") (pinfunction "G_G") (pintype "passive"))
      (node (ref "Q24") (pin "G") (pinfunction "G_G") (pintype "passive"))
      (node (ref "RGS-2") (pin "2") (pinfunction "2_2") (pintype "passive"))
    )
    (net (code "24") (name "GS1") (class "Default")
      (node (ref "Q1") (pin "3") (pinfunction "D_3") (pintype "passive"))
      (node (ref "Q11") (pin "G") (pinfunction "G_G") (pintype "passive"))
      (node (ref "Q12") (pin "G") (pinfunction "G_G") (pintype "passive"))
      (node (ref "Q14") (pin "G") (pinfunction "G_G") (pintype "passive"))
      (node (ref "RGS1") (pin "2") (pinfunction "2_2") (pintype "passive"))
    )
    (net (code "25") (name "GS3") (class "Default")
      (node (ref "Q31") (pin "G") (pinfunction "G_G") (pintype "passive"))
      (node (ref "Q32") (pin "G") (pinfunction "G_G") (pintype "passive"))
      (node (ref "Q33") (pin "G") (pinfunction "G_G") (pintype "passive"))
      (node (ref "Q34") (pin "G") (pinfunction "G_G") (pintype "passive"))
      (node (ref "RGS3") (pin "2") (pinfunction "2_2") (pintype "passive"))
      (node (ref "U1") (pin "3") (pinfunction "S2_3") (pintype "passive"))
    )
    (net (code "26") (name "GS4") (class "Default")
      (node (ref "Q41") (pin "G") (pinfunction "G_G") (pintype "passive"))
      (node (ref "Q42") (pin "G") (pinfunction "G_G") (pintype "passive"))
      (node (ref "Q43") (pin "G") (pinfunction "G_G") (pintype "passive"))
      (node (ref "Q44") (pin "G") (pinfunction "G_G") (pintype "passive"))
      (node (ref "RGS4") (pin "2") (pinfunction "2_2") (pintype "passive"))
      (node (ref "U1") (pin "4") (pinfunction "S3_4") (pintype "passive"))
    )
    (net (code "27") (name "GS5") (class "Default")
      (node (ref "Q51") (pin "G") (pinfunction "G_G") (pintype "passive"))
      (node (ref "Q52") (pin "G") (pinfunction "G_G") (pintype "passive"))
      (node (ref "Q53") (pin "G") (pinfunction "G_G") (pintype "passive"))
      (node (ref "Q54") (pin "G") (pinfunction "G_G") (pintype "passive"))
      (node (ref "RGS5") (pin "2") (pinfunction "2_2") (pintype "passive"))
      (node (ref "U1") (pin "5") (pinfunction "S4_5") (pintype "passive"))
    )
    (net (code "28") (name "GS6") (class "Default")
      (node (ref "Q62") (pin "G") (pinfunction "G_G") (pintype "passive"))
      (node (ref "Q64") (pin "G") (pinfunction "G_G") (pintype "passive"))
      (node (ref "RGS6") (pin "2") (pinfunction "2_2") (pintype "passive"))
      (node (ref "U1") (pin "10") (pinfunction "S5_10") (pintype "passive"))
      (node (ref "U1") (pin "7") (pinfunction "S8_7") (pintype "passive"))
      (node (ref "U1") (pin "8") (pinfunction "S7_8") (pintype "passive"))
      (node (ref "U1") (pin "9") (pinfunction "S6_9") (pintype "passive"))
    )
    (net (code "29") (name "GT+2") (class "Default")
      (node (ref "Q25") (pin "G") (pinfunction "G_G") (pintype "passive"))
      (node (ref "Q26") (pin "G") (pinfunction "G_G") (pintype "passive"))
      (node (ref "Q3") (pin "5") (pinfunction "G_5") (pintype "passive"))
      (node (ref "RGT+2") (pin "2") (pinfunction "2_2") (pintype "passive"))
      (node (ref "U2") (pin "4") (pinfunction "S3_4") (pintype "passive"))
    )
    (net (code "30") (name "GT-2") (class "Default")
      (node (ref "Q27") (pin "G") (pinfunction "G_G") (pintype "passive"))
      (node (ref "Q28") (pin "G") (pinfunction "G_G") (pintype "passive"))
      (node (ref "Q3") (pin "3") (pinfunction "D_3") (pintype "passive"))
      (node (ref "RGT-2") (pin "2") (pinfunction "2_2") (pintype "passive"))
    )
    (net (code "31") (name "GT1") (class "Default")
      (node (ref "Q15") (pin "G") (pinfunction "G_G") (pintype "passive"))
      (node (ref "Q16") (pin "G") (pinfunction "G_G") (pintype "passive"))
      (node (ref "Q18") (pin "G") (pinfunction "G_G") (pintype "passive"))
      (node (ref "Q3") (pin "6") (pinfunction "D_6") (pintype "passive"))
      (node (ref "RGT1") (pin "2") (pinfunction "2_2") (pintype "passive"))
    )
    (net (code "32") (name "GT3") (class "Default")
      (node (ref "Q35") (pin "G") (pinfunction "G_G") (pintype "passive"))
      (node (ref "Q36") (pin "G") (pinfunction "G_G") (pintype "passive"))
      (node (ref "Q37") (pin "G") (pinfunction "G_G") (pintype "passive"))
      (node (ref "Q38") (pin "G") (pinfunction "G_G") (pintype "passive"))
      (node (ref "RGT3") (pin "2") (pinfunction "2_2") (pintype "passive"))
      (node (ref "U2") (pin "5") (pinfunction "S4_5") (pintype "passive"))
    )
    (net (code "33") (name "GT4") (class "Default")
      (node (ref "Q45") (pin "G") (pinfunction "G_G") (pintype "passive"))
      (node (ref "Q46") (pin "G") (pinfunction "G_G") (pintype "passive"))
      (node (ref "Q47") (pin "G") (pinfunction "G_G") (pintype "passive"))
      (node (ref "Q48") (pin "G") (pinfunction "G_G") (pintype "passive"))
      (node (ref "RGT4") (pin "2") (pinfunction "2_2") (pintype "passive"))
      (node (ref "U2") (pin "10") (pinfunction "S5_10") (pintype "passive"))
    )
    (net (code "34") (name "GT5") (class "Default")
      (node (ref "Q55") (pin "G") (pinfunction "G_G") (pintype "passive"))
      (node (ref "Q56") (pin "G") (pinfunction "G_G") (pintype "passive"))
      (node (ref "Q57") (pin "G") (pinfunction "G_G") (pintype "passive"))
      (node (ref "Q58") (pin "G") (pinfunction "G_G") (pintype "passive"))
      (node (ref "RGT5") (pin "2") (pinfunction "2_2") (pintype "passive"))
      (node (ref "U2") (pin "9") (pinfunction "S6_9") (pintype "passive"))
    )
    (net (code "35") (name "GT6") (class "Default")
      (node (ref "Q66") (pin "G") (pinfunction "G_G") (pintype "passive"))
      (node (ref "Q68") (pin "G") (pinfunction "G_G") (pintype "passive"))
      (node (ref "RGT6") (pin "2") (pinfunction "2_2") (pintype "passive"))
      (node (ref "U2") (pin "7") (pinfunction "S8_7") (pintype "passive"))
      (node (ref "U2") (pin "8") (pinfunction "S7_8") (pintype "passive"))
    )
    (net (code "36") (name "N$1") (class "Default")
      (node (ref "U3") (pin "7") (pinfunction "Q7_7") (pintype "passive"))
    )
    (net (code "37") (name "N$19") (class "Default")
      (node (ref "U3") (pin "9") (pinfunction "Q7S_9") (pintype "passive"))
    )
    (net (code "38") (name "Net-(D11-PadA)") (class "Default")
      (node (ref "D11") (pin "A") (pinfunction "A_A") (pintype "passive"))
      (node (ref "D21") (pin "A") (pinfunction "A_A") (pintype "passive"))
      (node (ref "D31") (pin "A") (pinfunction "A_A") (pintype "passive"))
      (node (ref "D41") (pin "A") (pinfunction "A_A") (pintype "passive"))
      (node (ref "D51") (pin "A") (pinfunction "A_A") (pintype "passive"))
      (node (ref "D61") (pin "A") (pinfunction "A_A") (pintype "passive"))
      (node (ref "U10") (pin "C") (pinfunction "C_C") (pintype "passive"))
    )
    (net (code "39") (name "Net-(Q3A-G)") (class "Default")
      (node (ref "Q3") (pin "2") (pinfunction "G_2") (pintype "passive"))
      (node (ref "U2") (pin "3") (pinfunction "S2_3") (pintype "passive"))
    )
    (net (code "40") (name "Net-(Q11-PadS)") (class "Default")
      (node (ref "Q11") (pin "S") (pinfunction "S_S") (pintype "passive"))
      (node (ref "Q12") (pin "S") (pinfunction "S_S") (pintype "passive"))
    )
    (net (code "41") (name "Net-(Q15-PadS)") (class "Default")
      (node (ref "Q15") (pin "S") (pinfunction "S_S") (pintype "passive"))
      (node (ref "Q16") (pin "S") (pinfunction "S_S") (pintype "passive"))
    )
    (net (code "42") (name "Net-(Q21-PadS)") (class "Default")
      (node (ref "Q21") (pin "S") (pinfunction "S_S") (pintype "passive"))
      (node (ref "Q22") (pin "S") (pinfunction "S_S") (pintype "passive"))
    )
    (net (code "43") (name "Net-(Q23-PadS)") (class "Default")
      (node (ref "Q23") (pin "S") (pinfunction "S_S") (pintype "passive"))
      (node (ref "Q24") (pin "S") (pinfunction "S_S") (pintype "passive"))
    )
    (net (code "44") (name "Net-(Q25-PadS)") (class "Default")
      (node (ref "Q25") (pin "S") (pinfunction "S_S") (pintype "passive"))
      (node (ref "Q26") (pin "S") (pinfunction "S_S") (pintype "passive"))
    )
    (net (code "45") (name "Net-(Q27-PadS)") (class "Default")
      (node (ref "Q27") (pin "S") (pinfunction "S_S") (pintype "passive"))
      (node (ref "Q28") (pin "S") (pinfunction "S_S") (pintype "passive"))
    )
    (net (code "46") (name "Net-(Q31-PadS)") (class "Default")
      (node (ref "Q31") (pin "S") (pinfunction "S_S") (pintype "passive"))
      (node (ref "Q32") (pin "S") (pinfunction "S_S") (pintype "passive"))
    )
    (net (code "47") (name "Net-(Q33-PadS)") (class "Default")
      (node (ref "Q33") (pin "S") (pinfunction "S_S") (pintype "passive"))
      (node (ref "Q34") (pin "S") (pinfunction "S_S") (pintype "passive"))
    )
    (net (code "48") (name "Net-(Q35-PadS)") (class "Default")
      (node (ref "Q35") (pin "S") (pinfunction "S_S") (pintype "passive"))
      (node (ref "Q36") (pin "S") (pinfunction "S_S") (pintype "passive"))
    )
    (net (code "49") (name "Net-(Q37-PadS)") (class "Default")
      (node (ref "Q37") (pin "S") (pinfunction "S_S") (pintype "passive"))
      (node (ref "Q38") (pin "S") (pinfunction "S_S") (pintype "passive"))
    )
    (net (code "50") (name "Net-(Q41-PadS)") (class "Default")
      (node (ref "Q41") (pin "S") (pinfunction "S_S") (pintype "passive"))
      (node (ref "Q42") (pin "S") (pinfunction "S_S") (pintype "passive"))
    )
    (net (code "51") (name "Net-(Q43-PadS)") (class "Default")
      (node (ref "Q43") (pin "S") (pinfunction "S_S") (pintype "passive"))
      (node (ref "Q44") (pin "S") (pinfunction "S_S") (pintype "passive"))
    )
    (net (code "52") (name "Net-(Q45-PadS)") (class "Default")
      (node (ref "Q45") (pin "S") (pinfunction "S_S") (pintype "passive"))
      (node (ref "Q46") (pin "S") (pinfunction "S_S") (pintype "passive"))
    )
    (net (code "53") (name "Net-(Q47-PadS)") (class "Default")
      (node (ref "Q47") (pin "S") (pinfunction "S_S") (pintype "passive"))
      (node (ref "Q48") (pin "S") (pinfunction "S_S") (pintype "passive"))
    )
    (net (code "54") (name "Net-(Q51-PadS)") (class "Default")
      (node (ref "Q51") (pin "S") (pinfunction "S_S") (pintype "passive"))
      (node (ref "Q52") (pin "S") (pinfunction "S_S") (pintype "passive"))
    )
    (net (code "55") (name "Net-(Q53-PadS)") (class "Default")
      (node (ref "Q53") (pin "S") (pinfunction "S_S") (pintype "passive"))
      (node (ref "Q54") (pin "S") (pinfunction "S_S") (pintype "passive"))
    )
    (net (code "56") (name "Net-(Q55-PadS)") (class "Default")
      (node (ref "Q55") (pin "S") (pinfunction "S_S") (pintype "passive"))
      (node (ref "Q56") (pin "S") (pinfunction "S_S") (pintype "passive"))
    )
    (net (code "57") (name "Net-(Q57-PadS)") (class "Default")
      (node (ref "Q57") (pin "S") (pinfunction "S_S") (pintype "passive"))
      (node (ref "Q58") (pin "S") (pinfunction "S_S") (pintype "passive"))
    )
    (net (code "58") (name "Net-(T1-5)") (class "Default")
      (node (ref "T1") (pin "6") (pinfunction "7_6") (pintype "passive"))
      (node (ref "T1") (pin "7") (pinfunction "5_7") (pintype "passive"))
      (node (ref "U$8") (pin "D") (pinfunction "D_D") (pintype "passive"))
    )
    (net (code "59") (name "Net-(U3-~{MR})") (class "Default")
      (node (ref "R4") (pin "2") (pinfunction "2_2") (pintype "passive"))
      (node (ref "U3") (pin "10") (pinfunction "~{MR}_10") (pintype "passive"))
    )
    (net (code "60") (name "Net-(U4-GATE)") (class "Default")
      (node (ref "U$8") (pin "G") (pinfunction "G_G") (pintype "passive"))
      (node (ref "U4") (pin "7") (pinfunction "GATE_7") (pintype "passive"))
    )
    (net (code "61") (name "Net-(U4-INTVCC)") (class "Default")
      (node (ref "U4") (pin "10") (pinfunction "VIN_10") (pintype "power_in"))
      (node (ref "U4") (pin "8") (pinfunction "INTVCC_8") (pintype "passive"))
      (node (ref "U4") (pin "9") (pinfunction "~{SHDN}_9") (pintype "passive"))
      (node (ref "U5") (pin "5") (pinfunction "VOUT_5") (pintype "power_in"))
    )
    (net (code "62") (name "Net-(U4-SENSE)") (class "Default")
      (node (ref "R5") (pin "2") (pinfunction "2_2") (pintype "passive"))
      (node (ref "U$8") (pin "S") (pinfunction "S_S") (pintype "passive"))
      (node (ref "U4") (pin "6") (pinfunction "SENSE_6") (pintype "passive"))
    )
    (net (code "63") (name "Net-(U5-C+)") (class "Default")
      (node (ref "C1") (pin "2") (pinfunction "2_2") (pintype "passive"))
      (node (ref "U5") (pin "6") (pinfunction "C+_6") (pintype "passive"))
    )
    (net (code "64") (name "Net-(U5-C-)") (class "Default")
      (node (ref "C1") (pin "1") (pinfunction "1_1") (pintype "passive"))
      (node (ref "U5") (pin "3") (pinfunction "C-_3") (pintype "passive"))
    )
    (net (code "65") (name "S+") (class "Default")
      (node (ref "D2") (pin "1") (pinfunction "A_1") (pintype "passive"))
      (node (ref "D2") (pin "2") (pinfunction "A_2") (pintype "passive"))
      (node (ref "Q12") (pin "D") (pinfunction "D_D") (pintype "passive"))
      (node (ref "Q22") (pin "D") (pinfunction "D_D") (pintype "passive"))
      (node (ref "Q32") (pin "D") (pinfunction "D_D") (pintype "passive"))
      (node (ref "Q42") (pin "D") (pinfunction "D_D") (pintype "passive"))
      (node (ref "Q52") (pin "D") (pinfunction "D_D") (pintype "passive"))
      (node (ref "Q62") (pin "D") (pinfunction "D_D") (pintype "passive"))
      (node (ref "R1") (pin "2") (pinfunction "2_2") (pintype "passive"))
      (node (ref "T1") (pin "10") (pinfunction "6_10") (pintype "passive"))
      (node (ref "T1") (pin "9") (pinfunction "8_9") (pintype "passive"))
      (node (ref "U5") (pin "1") (pinfunction "VIN_1") (pintype "power_in"))
    )
    (net (code "66") (name "S-") (class "Default")
      (node (ref "Q14") (pin "D") (pinfunction "D_D") (pintype "passive"))
      (node (ref "Q24") (pin "D") (pinfunction "D_D") (pintype "passive"))
      (node (ref "Q34") (pin "D") (pinfunction "D_D") (pintype "passive"))
      (node (ref "Q44") (pin "D") (pinfunction "D_D") (pintype "passive"))
      (node (ref "Q54") (pin "D") (pinfunction "D_D") (pintype "passive"))
      (node (ref "Q64") (pin "D") (pinfunction "D_D") (pintype "passive"))
      (node (ref "R1") (pin "1") (pinfunction "1_1") (pintype "passive"))
      (node (ref "R4") (pin "1") (pinfunction "1_1") (pintype "passive"))
      (node (ref "R5") (pin "1") (pinfunction "1_1") (pintype "passive"))
      (node (ref "U$1") (pin "C") (pinfunction "C_C") (pintype "passive"))
      (node (ref "U1") (pin "12") (pinfunction "GND_12") (pintype "passive"))
      (node (ref "U2") (pin "12") (pinfunction "GND_12") (pintype "passive"))
      (node (ref "U3") (pin "8") (pinfunction "GND_8") (pintype "passive"))
      (node (ref "U3") (pin "PAD") (pinfunction "GND_PAD") (pintype "passive"))
      (node (ref "U4") (pin "5") (pinfunction "SYNC_5") (pintype "passive"))
      (node (ref "U4") (pin "PAD") (pinfunction "GND_PAD") (pintype "power_in"))
      (node (ref "U5") (pin "2") (pinfunction "GND_2") (pintype "power_in"))
      (node (ref "U5") (pin "4") (pinfunction "SHDN_4") (pintype "passive"))
    )
    (net (code "67") (name "T+") (class "Default")
      (node (ref "Q16") (pin "D") (pinfunction "D_D") (pintype "passive"))
      (node (ref "Q26") (pin "D") (pinfunction "D_D") (pintype "passive"))
      (node (ref "Q36") (pin "D") (pinfunction "D_D") (pintype "passive"))
      (node (ref "Q46") (pin "D") (pinfunction "D_D") (pintype "passive"))
      (node (ref "Q56") (pin "D") (pinfunction "D_D") (pintype "passive"))
      (node (ref "Q66") (pin "D") (pinfunction "D_D") (pintype "passive"))
      (node (ref "R2") (pin "2") (pinfunction "2_2") (pintype "passive"))
    )
    (net (code "68") (name "T-") (class "Default")
      (node (ref "Q18") (pin "D") (pinfunction "D_D") (pintype "passive"))
      (node (ref "Q28") (pin "D") (pinfunction "D_D") (pintype "passive"))
      (node (ref "Q38") (pin "D") (pinfunction "D_D") (pintype "passive"))
      (node (ref "Q48") (pin "D") (pinfunction "D_D") (pintype "passive"))
      (node (ref "Q58") (pin "D") (pinfunction "D_D") (pintype "passive"))
      (node (ref "Q68") (pin "D") (pinfunction "D_D") (pintype "passive"))
      (node (ref "R2") (pin "1") (pinfunction "1_1") (pintype "passive"))
      (node (ref "T1") (pin "1") (pinfunction "1_1") (pintype "passive"))
      (node (ref "T1") (pin "4") (pinfunction "3_4") (pintype "passive"))
    )
    (net (code "69") (name "VCC") (class "Default")
      (node (ref "D2") (pin "7") (pinfunction "C_7") (pintype "passive"))
      (node (ref "D2") (pin "8") (pinfunction "C_8") (pintype "passive"))
      (node (ref "R3") (pin "1") (pinfunction "1_1") (pintype "passive"))
      (node (ref "U$1") (pin "A") (pinfunction "A_A") (pintype "passive"))
      (node (ref "U3") (pin "16") (pinfunction "VCC_16") (pintype "passive"))
    )
    (net (code "70") (name "unconnected-(D11-PadC)") (class "Default")
      (node (ref "D11") (pin "C") (pinfunction "C_C") (pintype "passive"))
    )
    (net (code "71") (name "unconnected-(D21-PadC)") (class "Default")
      (node (ref "D21") (pin "C") (pinfunction "C_C") (pintype "passive"))
    )
    (net (code "72") (name "unconnected-(D31-PadC)") (class "Default")
      (node (ref "D31") (pin "C") (pinfunction "C_C") (pintype "passive"))
    )
    (net (code "73") (name "unconnected-(D41-PadC)") (class "Default")
      (node (ref "D41") (pin "C") (pinfunction "C_C") (pintype "passive"))
    )
    (net (code "74") (name "unconnected-(D51-PadC)") (class "Default")
      (node (ref "D51") (pin "C") (pinfunction "C_C") (pintype "passive"))
    )
    (net (code "75") (name "unconnected-(D61-PadC)") (class "Default")
      (node (ref "D61") (pin "C") (pinfunction "C_C") (pintype "passive"))
    )
    (net (code "76") (name "unconnected-(T1-4-Pad5)") (class "Default")
      (node (ref "T1") (pin "5") (pinfunction "4_5") (pintype "passive"))
    )
    (net (code "77") (name "unconnected-(U4-RT-Pad4)") (class "Default")
      (node (ref "U4") (pin "4") (pinfunction "RT_4") (pintype "passive"))
    )
    (net (code "78") (name "unconnected-(U4-SS-Pad3)") (class "Default")
      (node (ref "U4") (pin "3") (pinfunction "SS_3") (pintype "passive"))
    )
    (net (code "79") (name "unconnected-(U4-VC-Pad1)") (class "Default")
      (node (ref "U4") (pin "1") (pinfunction "VC_1") (pintype "passive"))
    )
  )
)
